# 1___MCU.net
KiCad netlist of a schematic drawn in Altium Designer
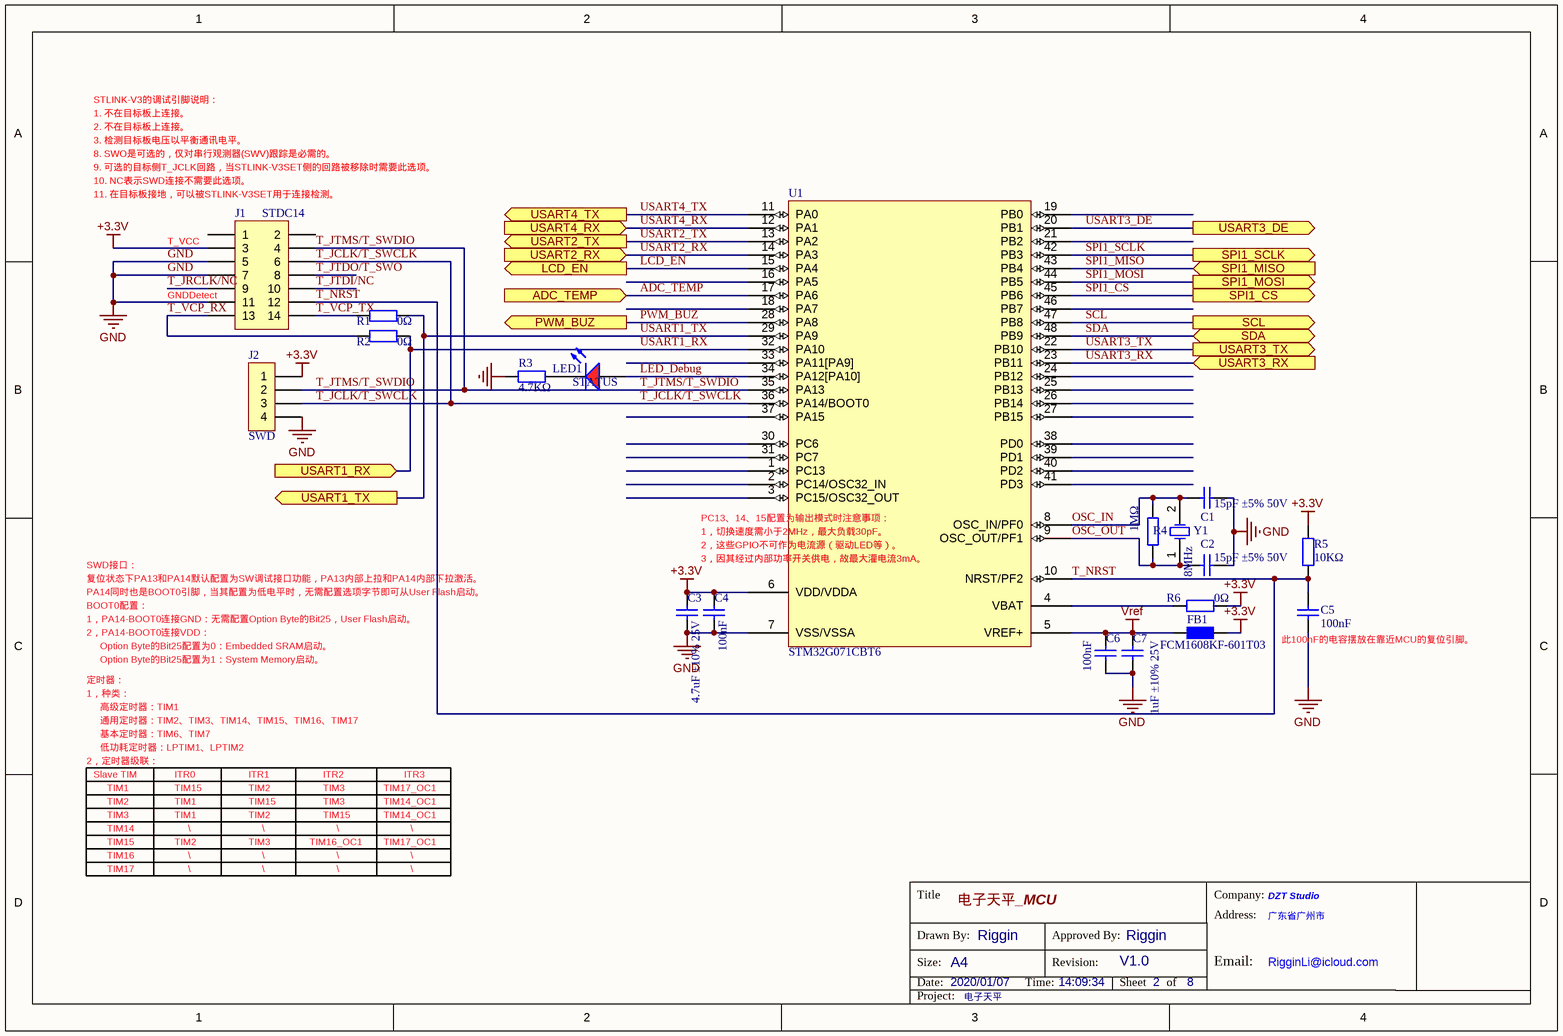
[diagram p0: 1_电子天平_MCU.SchDoc]

(export (version "E")
  (design (tool "Eeschema 10.0.6"))
  (components
    (comp (ref "C1")
      (value "15pF ±5% 50V")
      (footprint "LC-0805_C")
      (description "MLCC NP0")
      (fields (field (name "PUBLISHER") "Altium Limited"))
      (libsource (lib "Miscellaneous Devices") (part "Cap"))
    )
    (comp (ref "C2")
      (value "15pF ±5% 50V")
      (footprint "LC-0805_C")
      (description "MLCC NP0")
      (fields (field (name "PUBLISHER") "Altium Limited"))
      (libsource (lib "Miscellaneous Devices") (part "Cap"))
    )
    (comp (ref "C3")
      (value "4.7uF ±10% 25V")
      (footprint "LC-0805_C")
      (description "MLCC")
      (fields (field (name "PUBLISHER") "Altium Limited"))
      (libsource (lib "Miscellaneous Devices") (part "Cap"))
    )
    (comp (ref "C4")
      (value "100nF")
      (footprint "LC-0805_C")
      (description "MLCC")
      (fields (field (name "PUBLISHER") "Altium Limited"))
      (libsource (lib "Miscellaneous Devices") (part "Cap"))
    )
    (comp (ref "C5")
      (value "100nF")
      (footprint "LC-0805_C")
      (description "MLCC")
      (fields (field (name "PUBLISHER") "Altium Limited"))
      (libsource (lib "Miscellaneous Devices") (part "Cap"))
    )
    (comp (ref "C6")
      (value "100nF")
      (footprint "LC-0805_C")
      (description "MLCC")
      (fields (field (name "PUBLISHER") "Altium Limited"))
      (libsource (lib "Miscellaneous Devices") (part "Cap"))
    )
    (comp (ref "C7")
      (value "1uF ±10% 25V")
      (footprint "LC-0805_C")
      (description "MLCC")
      (fields (field (name "PUBLISHER") "Altium Limited"))
      (libsource (lib "Miscellaneous Devices") (part "Cap"))
    )
    (comp (ref "FB1")
      (value "FCM1608KF-601T03")
      (footprint "LC-0603_L")
      (description "磁珠")
      (libsource (lib "Riggin") (part "FB"))
    )
    (comp (ref "J1")
      (value "STDC14")
      (footprint "CON-FTSH-107-01-L-DV-K")
      (description "Header, 7-Pin, Dual row")
      (fields (field (name "PUBLISHER") "Altium Limited"))
      (libsource (lib "Miscellaneous Connectors") (part "Header 7X2"))
    )
    (comp (ref "J2") (value "SWD") (footprint "CON-PH2.0-4P-DIP") (libsource (lib "Wuyingjie") (part "SIP4")))
    (comp (ref "LED1")
      (value "STATUS")
      (footprint "LC-0805_LED_S1")
      (description "LED")
      (libsource (lib "Miscellaneous Devices LC") (part "0603 红灯"))
    )
    (comp (ref "R1")
      (value "0Ω")
      (footprint "LC-0805_R")
      (description "Resistor")
      (fields (field (name "PUBLISHER") "Altium Limited"))
      (libsource (lib "Miscellaneous Devices") (part "Res2"))
    )
    (comp (ref "R2")
      (value "0Ω")
      (footprint "LC-0805_R")
      (description "Resistor")
      (fields (field (name "PUBLISHER") "Altium Limited"))
      (libsource (lib "Miscellaneous Devices") (part "Res2"))
    )
    (comp (ref "R3")
      (value "4.7KΩ")
      (footprint "LC-0805_R")
      (description "Resistor")
      (fields (field (name "PUBLISHER") "Altium Limited"))
      (libsource (lib "Miscellaneous Devices") (part "Res2"))
    )
    (comp (ref "R4")
      (value "1MΩ")
      (footprint "LC-0805_R")
      (description "Resistor")
      (fields (field (name "PUBLISHER") "Altium Limited"))
      (libsource (lib "") (part "Res2_2"))
    )
    (comp (ref "R5")
      (value "10KΩ")
      (footprint "LC-0805_R")
      (description "Resistor")
      (fields (field (name "PUBLISHER") "Altium Limited"))
      (libsource (lib "") (part "Res2_2"))
    )
    (comp (ref "R6")
      (value "0Ω")
      (footprint "LC-0805_R")
      (description "Resistor")
      (fields (field (name "PUBLISHER") "Altium Limited"))
      (libsource (lib "") (part "Res2_1"))
    )
    (comp (ref "U1")
      (value "STM32G071CBT6")
      (footprint "LC-LQFP-48_7x7x05P")
      (description "128KB Flash, 36KB RAM, 4USART,timers,ADC,DAC,comm. I/Fs,AES-256,1.65-3.6V")
      (libsource (lib "Riggin") (part "STM32G081CBT6"))
    )
    (comp (ref "Y1")
      (value "8MHz")
      (footprint "3225_XT_2P")
      (description "SMD 8MHz")
      (libsource (lib "Miscellaneous Devices LC") (part "SMD-5032_2P 8MHz 20ppm 20pF"))
    )
  )
  (nets
    (net (code "1") (name "+3.3V") (class "Default")
      (node (ref "C3") (pin "1") (pinfunction "1_1") (pintype "passive"))
      (node (ref "C4") (pin "1") (pinfunction "1_1") (pintype "passive"))
      (node (ref "FB1") (pin "1") (pinfunction "1_1") (pintype "passive"))
      (node (ref "J1") (pin "3") (pinfunction "3_3") (pintype "passive"))
      (node (ref "J2") (pin "1") (pinfunction "1_1") (pintype "passive"))
      (node (ref "R5") (pin "2") (pinfunction "2_2") (pintype "passive"))
      (node (ref "R6") (pin "1") (pinfunction "1_1") (pintype "passive"))
      (node (ref "U1") (pin "6") (pinfunction "VDD/VDDA_6") (pintype "power_in"))
    )
    (net (code "2") (name "/ADC_TEMP") (class "Default")
      (node (ref "U1") (pin "17") (pinfunction "PA6_17") (pintype "bidirectional"))
    )
    (net (code "3") (name "/LCD_EN") (class "Default")
      (node (ref "U1") (pin "15") (pinfunction "PA4_15") (pintype "bidirectional"))
    )
    (net (code "4") (name "/LED_Debug") (class "Default")
      (node (ref "LED1") (pin "A") (pinfunction "A_A") (pintype "passive"))
      (node (ref "U1") (pin "34") (pinfunction "PA12[PA10]_34") (pintype "bidirectional"))
    )
    (net (code "5") (name "/OSC_IN") (class "Default")
      (node (ref "C1") (pin "2") (pinfunction "2_2") (pintype "passive"))
      (node (ref "R4") (pin "2") (pinfunction "2_2") (pintype "passive"))
      (node (ref "U1") (pin "8") (pinfunction "OSC_IN/PF0_8") (pintype "bidirectional"))
      (node (ref "Y1") (pin "2") (pinfunction "OSC2_2") (pintype "passive"))
    )
    (net (code "6") (name "/OSC_OUT") (class "Default")
      (node (ref "C2") (pin "2") (pinfunction "2_2") (pintype "passive"))
      (node (ref "R4") (pin "1") (pinfunction "1_1") (pintype "passive"))
      (node (ref "U1") (pin "9") (pinfunction "OSC_OUT/PF1_9") (pintype "bidirectional"))
      (node (ref "Y1") (pin "1") (pinfunction "OSC1_1") (pintype "passive"))
    )
    (net (code "7") (name "/PWM_BUZ") (class "Default")
      (node (ref "U1") (pin "28") (pinfunction "PA8_28") (pintype "bidirectional"))
    )
    (net (code "8") (name "/SCL") (class "Default")
      (node (ref "U1") (pin "47") (pinfunction "PB8_47") (pintype "bidirectional"))
    )
    (net (code "9") (name "/SDA") (class "Default")
      (node (ref "U1") (pin "48") (pinfunction "PB9_48") (pintype "bidirectional"))
    )
    (net (code "10") (name "/SPI1_CS") (class "Default")
      (node (ref "U1") (pin "45") (pinfunction "PB6_45") (pintype "bidirectional"))
    )
    (net (code "11") (name "/SPI1_MISO") (class "Default")
      (node (ref "U1") (pin "43") (pinfunction "PB4_43") (pintype "bidirectional"))
    )
    (net (code "12") (name "/SPI1_MOSI") (class "Default")
      (node (ref "U1") (pin "44") (pinfunction "PB5_44") (pintype "bidirectional"))
    )
    (net (code "13") (name "/SPI1_SCLK") (class "Default")
      (node (ref "U1") (pin "42") (pinfunction "PB3_42") (pintype "bidirectional"))
    )
    (net (code "14") (name "/T_JCLK{slash}T_SWCLK") (class "Default")
      (node (ref "J1") (pin "6") (pinfunction "6_6") (pintype "passive"))
      (node (ref "J2") (pin "3") (pinfunction "3_3") (pintype "passive"))
      (node (ref "U1") (pin "36") (pinfunction "PA14/BOOT0_36") (pintype "bidirectional"))
    )
    (net (code "15") (name "/T_JRCLK{slash}NC") (class "Default")
      (node (ref "J1") (pin "9") (pinfunction "9_9") (pintype "passive"))
    )
    (net (code "16") (name "/T_JTDI{slash}NC") (class "Default")
      (node (ref "J1") (pin "10") (pinfunction "10_10") (pintype "passive"))
    )
    (net (code "17") (name "/T_JTDO{slash}T_SWO") (class "Default")
      (node (ref "J1") (pin "8") (pinfunction "8_8") (pintype "passive"))
    )
    (net (code "18") (name "/T_JTMS{slash}T_SWDIO") (class "Default")
      (node (ref "J1") (pin "4") (pinfunction "4_4") (pintype "passive"))
      (node (ref "J2") (pin "2") (pinfunction "2_2") (pintype "passive"))
      (node (ref "U1") (pin "35") (pinfunction "PA13_35") (pintype "bidirectional"))
    )
    (net (code "19") (name "/T_NRST") (class "Default")
      (node (ref "C5") (pin "1") (pinfunction "1_1") (pintype "passive"))
      (node (ref "J1") (pin "12") (pinfunction "12_12") (pintype "passive"))
      (node (ref "R5") (pin "1") (pinfunction "1_1") (pintype "passive"))
      (node (ref "U1") (pin "10") (pinfunction "NRST/PF2_10") (pintype "bidirectional"))
    )
    (net (code "20") (name "/T_VCP_RX") (class "Default")
      (node (ref "J1") (pin "13") (pinfunction "13_13") (pintype "passive"))
      (node (ref "R2") (pin "2") (pinfunction "2_2") (pintype "passive"))
    )
    (net (code "21") (name "/T_VCP_TX") (class "Default")
      (node (ref "J1") (pin "14") (pinfunction "14_14") (pintype "passive"))
      (node (ref "R1") (pin "2") (pinfunction "2_2") (pintype "passive"))
    )
    (net (code "22") (name "/USART1_RX") (class "Default")
      (node (ref "R2") (pin "1") (pinfunction "1_1") (pintype "passive"))
      (node (ref "U1") (pin "32") (pinfunction "PA10_32") (pintype "bidirectional"))
    )
    (net (code "23") (name "/USART1_TX") (class "Default")
      (node (ref "R1") (pin "1") (pinfunction "1_1") (pintype "passive"))
      (node (ref "U1") (pin "29") (pinfunction "PA9_29") (pintype "bidirectional"))
    )
    (net (code "24") (name "/USART2_RX") (class "Default")
      (node (ref "U1") (pin "14") (pinfunction "PA3_14") (pintype "bidirectional"))
    )
    (net (code "25") (name "/USART2_TX") (class "Default")
      (node (ref "U1") (pin "13") (pinfunction "PA2_13") (pintype "bidirectional"))
    )
    (net (code "26") (name "/USART3_DE") (class "Default")
      (node (ref "U1") (pin "20") (pinfunction "PB1_20") (pintype "bidirectional"))
    )
    (net (code "27") (name "/USART3_RX") (class "Default")
      (node (ref "U1") (pin "23") (pinfunction "PB11_23") (pintype "bidirectional"))
    )
    (net (code "28") (name "/USART3_TX") (class "Default")
      (node (ref "U1") (pin "22") (pinfunction "PB10_22") (pintype "bidirectional"))
    )
    (net (code "29") (name "/USART4_RX") (class "Default")
      (node (ref "U1") (pin "12") (pinfunction "PA1_12") (pintype "bidirectional"))
    )
    (net (code "30") (name "/USART4_TX") (class "Default")
      (node (ref "U1") (pin "11") (pinfunction "PA0_11") (pintype "bidirectional"))
    )
    (net (code "31") (name "GND") (class "Default")
      (node (ref "C1") (pin "1") (pinfunction "1_1") (pintype "passive"))
      (node (ref "C2") (pin "1") (pinfunction "1_1") (pintype "passive"))
      (node (ref "C3") (pin "2") (pinfunction "2_2") (pintype "passive"))
      (node (ref "C4") (pin "2") (pinfunction "2_2") (pintype "passive"))
      (node (ref "C5") (pin "2") (pinfunction "2_2") (pintype "passive"))
      (node (ref "C6") (pin "2") (pinfunction "2_2") (pintype "passive"))
      (node (ref "C7") (pin "2") (pinfunction "2_2") (pintype "passive"))
      (node (ref "J1") (pin "11") (pinfunction "11_11") (pintype "passive"))
      (node (ref "J1") (pin "5") (pinfunction "5_5") (pintype "passive"))
      (node (ref "J1") (pin "7") (pinfunction "7_7") (pintype "passive"))
      (node (ref "J2") (pin "4") (pinfunction "4_4") (pintype "passive"))
      (node (ref "R3") (pin "2") (pinfunction "2_2") (pintype "passive"))
      (node (ref "U1") (pin "7") (pinfunction "VSS/VSSA_7") (pintype "power_in"))
    )
    (net (code "32") (name "Net-(LED1-PadK)") (class "Default")
      (node (ref "LED1") (pin "K") (pinfunction "K_K") (pintype "passive"))
      (node (ref "R3") (pin "1") (pinfunction "1_1") (pintype "passive"))
    )
    (net (code "33") (name "Net-(U1-VBAT)") (class "Default")
      (node (ref "R6") (pin "2") (pinfunction "2_2") (pintype "passive"))
      (node (ref "U1") (pin "4") (pinfunction "VBAT_4") (pintype "power_in"))
    )
    (net (code "34") (name "Vref") (class "Default")
      (node (ref "C6") (pin "1") (pinfunction "1_1") (pintype "passive"))
      (node (ref "C7") (pin "1") (pinfunction "1_1") (pintype "passive"))
      (node (ref "FB1") (pin "2") (pinfunction "2_2") (pintype "passive"))
      (node (ref "U1") (pin "5") (pinfunction "VREF+_5") (pintype "power_in"))
    )
    (net (code "35") (name "unconnected-(J1-Pad1)") (class "Default")
      (node (ref "J1") (pin "1") (pinfunction "1_1") (pintype "passive"))
    )
    (net (code "36") (name "unconnected-(J1-Pad2)") (class "Default")
      (node (ref "J1") (pin "2") (pinfunction "2_2") (pintype "passive"))
    )
    (net (code "37") (name "unconnected-(U1-PA5-Pad16)") (class "Default")
      (node (ref "U1") (pin "16") (pinfunction "PA5_16") (pintype "bidirectional"))
    )
    (net (code "38") (name "unconnected-(U1-PA7-Pad18)") (class "Default")
      (node (ref "U1") (pin "18") (pinfunction "PA7_18") (pintype "bidirectional"))
    )
    (net (code "39") (name "unconnected-(U1-PA11[PA9]-Pad33)") (class "Default")
      (node (ref "U1") (pin "33") (pinfunction "PA11[PA9]_33") (pintype "bidirectional"))
    )
    (net (code "40") (name "unconnected-(U1-PA15-Pad37)") (class "Default")
      (node (ref "U1") (pin "37") (pinfunction "PA15_37") (pintype "bidirectional"))
    )
    (net (code "41") (name "unconnected-(U1-PB0-Pad19)") (class "Default")
      (node (ref "U1") (pin "19") (pinfunction "PB0_19") (pintype "bidirectional"))
    )
    (net (code "42") (name "unconnected-(U1-PB2-Pad21)") (class "Default")
      (node (ref "U1") (pin "21") (pinfunction "PB2_21") (pintype "bidirectional"))
    )
    (net (code "43") (name "unconnected-(U1-PB7-Pad46)") (class "Default")
      (node (ref "U1") (pin "46") (pinfunction "PB7_46") (pintype "bidirectional"))
    )
    (net (code "44") (name "unconnected-(U1-PB12-Pad24)") (class "Default")
      (node (ref "U1") (pin "24") (pinfunction "PB12_24") (pintype "bidirectional"))
    )
    (net (code "45") (name "unconnected-(U1-PB13-Pad25)") (class "Default")
      (node (ref "U1") (pin "25") (pinfunction "PB13_25") (pintype "bidirectional"))
    )
    (net (code "46") (name "unconnected-(U1-PB14-Pad26)") (class "Default")
      (node (ref "U1") (pin "26") (pinfunction "PB14_26") (pintype "bidirectional"))
    )
    (net (code "47") (name "unconnected-(U1-PB15-Pad27)") (class "Default")
      (node (ref "U1") (pin "27") (pinfunction "PB15_27") (pintype "bidirectional"))
    )
    (net (code "48") (name "unconnected-(U1-PC6-Pad30)") (class "Default")
      (node (ref "U1") (pin "30") (pinfunction "PC6_30") (pintype "bidirectional"))
    )
    (net (code "49") (name "unconnected-(U1-PC7-Pad31)") (class "Default")
      (node (ref "U1") (pin "31") (pinfunction "PC7_31") (pintype "bidirectional"))
    )
    (net (code "50") (name "unconnected-(U1-PC13-Pad1)") (class "Default")
      (node (ref "U1") (pin "1") (pinfunction "PC13_1") (pintype "bidirectional"))
    )
    (net (code "51") (name "unconnected-(U1-PC14{slash}OSC32_IN-Pad2)") (class "Default")
      (node (ref "U1") (pin "2") (pinfunction "PC14/OSC32_IN_2") (pintype "bidirectional"))
    )
    (net (code "52") (name "unconnected-(U1-PC15{slash}OSC32_OUT-Pad3)") (class "Default")
      (node (ref "U1") (pin "3") (pinfunction "PC15/OSC32_OUT_3") (pintype "bidirectional"))
    )
    (net (code "53") (name "unconnected-(U1-PD0-Pad38)") (class "Default")
      (node (ref "U1") (pin "38") (pinfunction "PD0_38") (pintype "bidirectional"))
    )
    (net (code "54") (name "unconnected-(U1-PD1-Pad39)") (class "Default")
      (node (ref "U1") (pin "39") (pinfunction "PD1_39") (pintype "bidirectional"))
    )
    (net (code "55") (name "unconnected-(U1-PD2-Pad40)") (class "Default")
      (node (ref "U1") (pin "40") (pinfunction "PD2_40") (pintype "bidirectional"))
    )
    (net (code "56") (name "unconnected-(U1-PD3-Pad41)") (class "Default")
      (node (ref "U1") (pin "41") (pinfunction "PD3_41") (pintype "bidirectional"))
    )
  )
)
